# RAT_breakout020820.net
KiCad netlist of a schematic drawn in EAGLE
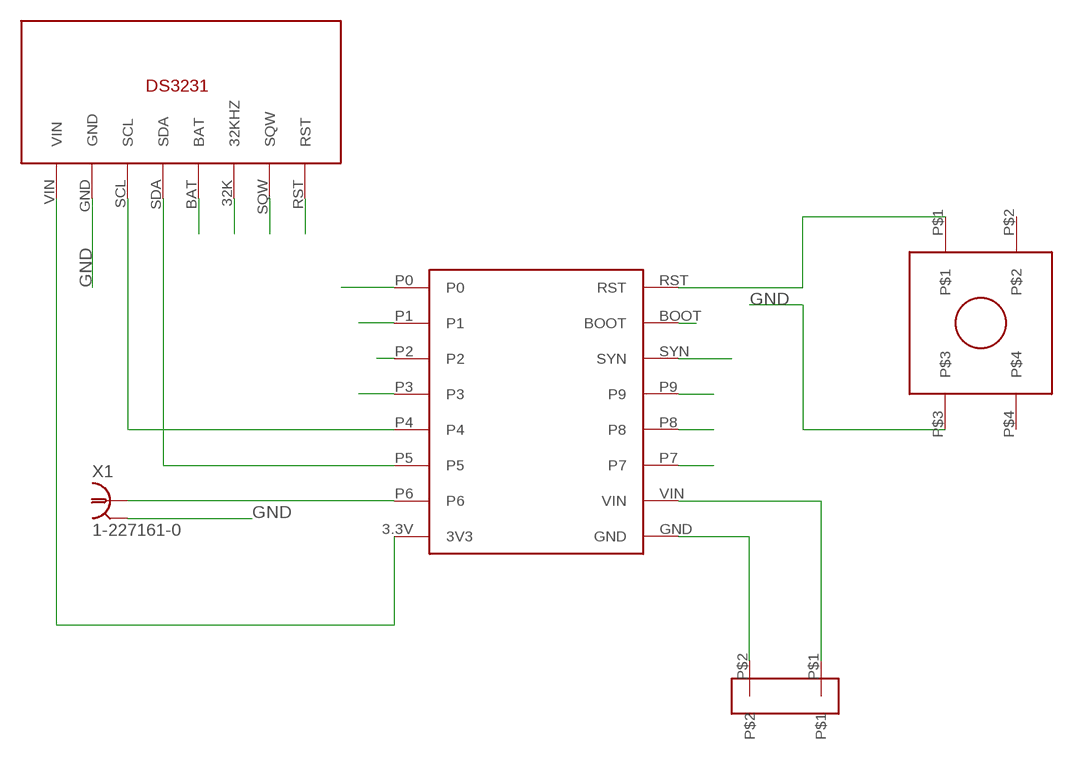
[diagram p0: schematic, sheet 1]

(export (version "E")
  (design (tool "Eeschema 10.0.6"))
  (components
    (comp (ref "U$1")
      (value "OPENMV_M7")
      (footprint "eagle-import:OPENMV_M7")
      (libsource (lib "eagle-import") (part "OPENMV_M7"))
    )
    (comp (ref "U$2")
      (value "JST_RA_PRT-09749")
      (footprint "eagle-import:JST_RA_PRT-09749")
      (libsource (lib "eagle-import") (part "JST_RA_PRT-09749"))
    )
    (comp (ref "U$3")
      (value "BTN_COM-10302")
      (footprint "eagle-import:BTN_COM-10302")
      (libsource (lib "eagle-import") (part "BTN_COM-10302"))
    )
    (comp (ref "U$6")
      (value "DS3231-RTC")
      (footprint "eagle-import:DS3231-RTC")
      (libsource (lib "eagle-import") (part "DS3231-RTC"))
    )
    (comp (ref "X1")
      (value "1-227161-0")
      (footprint "eagle-import:AMP_227161")
      (fields (field (name "MF") "TYCO ELECTRONICS") (field (name "MPN") "1-227161"))
      (libsource (lib "eagle-import") (part "?2271611--0"))
    )
  )
  (nets
    (net (code "1") (name "/GND") (class "Default")
      (node (ref "U$1") (pin "GND") (pinfunction "GND_GND") (pintype "bidirectional"))
      (node (ref "U$2") (pin "P$2") (pinfunction "P$2_P$2") (pintype "bidirectional"))
      (node (ref "U$3") (pin "P$3") (pinfunction "P$3_P$3") (pintype "bidirectional"))
      (node (ref "U$6") (pin "GND") (pinfunction "GND_GND") (pintype "bidirectional"))
      (node (ref "X1") (pin "2") (pinfunction "2_2") (pintype "passive"))
    )
    (net (code "2") (name "Net-(U$1-3V3)") (class "Default")
      (node (ref "U$1") (pin "3.3V") (pinfunction "3V3_3.3V") (pintype "bidirectional"))
      (node (ref "U$6") (pin "VIN") (pinfunction "VIN_VIN") (pintype "bidirectional"))
    )
    (net (code "3") (name "Net-(U$1-PadP4)") (class "Default")
      (node (ref "U$1") (pin "P4") (pinfunction "P4_P4") (pintype "bidirectional"))
      (node (ref "U$6") (pin "SCL") (pinfunction "SCL_SCL") (pintype "bidirectional"))
    )
    (net (code "4") (name "Net-(U$1-PadP5)") (class "Default")
      (node (ref "U$1") (pin "P5") (pinfunction "P5_P5") (pintype "bidirectional"))
      (node (ref "U$6") (pin "SDA") (pinfunction "SDA_SDA") (pintype "bidirectional"))
    )
    (net (code "5") (name "Net-(U$1-PadP6)") (class "Default")
      (node (ref "U$1") (pin "P6") (pinfunction "P6_P6") (pintype "bidirectional"))
      (node (ref "X1") (pin "1") (pinfunction "1_1") (pintype "passive"))
    )
    (net (code "6") (name "Net-(U$1-PadRST)") (class "Default")
      (node (ref "U$1") (pin "RST") (pinfunction "RST_RST") (pintype "bidirectional"))
      (node (ref "U$3") (pin "P$1") (pinfunction "P$1_P$1") (pintype "bidirectional"))
    )
    (net (code "7") (name "Net-(U$1-PadVIN)") (class "Default")
      (node (ref "U$1") (pin "VIN") (pinfunction "VIN_VIN") (pintype "bidirectional"))
      (node (ref "U$2") (pin "P$1") (pinfunction "P$1_P$1") (pintype "bidirectional"))
    )
    (net (code "8") (name "unconnected-(U$1-PadBOOT)") (class "Default")
      (node (ref "U$1") (pin "BOOT") (pinfunction "BOOT_BOOT") (pintype "bidirectional"))
    )
    (net (code "9") (name "unconnected-(U$1-PadP0)") (class "Default")
      (node (ref "U$1") (pin "P0") (pinfunction "P0_P0") (pintype "bidirectional"))
    )
    (net (code "10") (name "unconnected-(U$1-PadP1)") (class "Default")
      (node (ref "U$1") (pin "P1") (pinfunction "P1_P1") (pintype "bidirectional"))
    )
    (net (code "11") (name "unconnected-(U$1-PadP2)") (class "Default")
      (node (ref "U$1") (pin "P2") (pinfunction "P2_P2") (pintype "bidirectional"))
    )
    (net (code "12") (name "unconnected-(U$1-PadP3)") (class "Default")
      (node (ref "U$1") (pin "P3") (pinfunction "P3_P3") (pintype "bidirectional"))
    )
    (net (code "13") (name "unconnected-(U$1-PadP7)") (class "Default")
      (node (ref "U$1") (pin "P7") (pinfunction "P7_P7") (pintype "bidirectional"))
    )
    (net (code "14") (name "unconnected-(U$1-PadP8)") (class "Default")
      (node (ref "U$1") (pin "P8") (pinfunction "P8_P8") (pintype "bidirectional"))
    )
    (net (code "15") (name "unconnected-(U$1-PadP9)") (class "Default")
      (node (ref "U$1") (pin "P9") (pinfunction "P9_P9") (pintype "bidirectional"))
    )
    (net (code "16") (name "unconnected-(U$1-PadSYN)") (class "Default")
      (node (ref "U$1") (pin "SYN") (pinfunction "SYN_SYN") (pintype "bidirectional"))
    )
    (net (code "17") (name "unconnected-(U$3-PadP$2)") (class "Default")
      (node (ref "U$3") (pin "P$2") (pinfunction "P$2_P$2") (pintype "bidirectional"))
    )
    (net (code "18") (name "unconnected-(U$3-PadP$4)") (class "Default")
      (node (ref "U$3") (pin "P$4") (pinfunction "P$4_P$4") (pintype "bidirectional"))
    )
    (net (code "19") (name "unconnected-(U$6-32KHZ-Pad32K)") (class "Default")
      (node (ref "U$6") (pin "32K") (pinfunction "32KHZ_32K") (pintype "bidirectional"))
    )
    (net (code "20") (name "unconnected-(U$6-PadBAT)") (class "Default")
      (node (ref "U$6") (pin "BAT") (pinfunction "BAT_BAT") (pintype "bidirectional"))
    )
    (net (code "21") (name "unconnected-(U$6-PadRST)") (class "Default")
      (node (ref "U$6") (pin "RST") (pinfunction "RST_RST") (pintype "bidirectional"))
    )
    (net (code "22") (name "unconnected-(U$6-PadSQW)") (class "Default")
      (node (ref "U$6") (pin "SQW") (pinfunction "SQW_SQW") (pintype "bidirectional"))
    )
  )
)
